# TRC_ESP8266_v5.net
KiCad netlist of a schematic drawn in EasyEDA
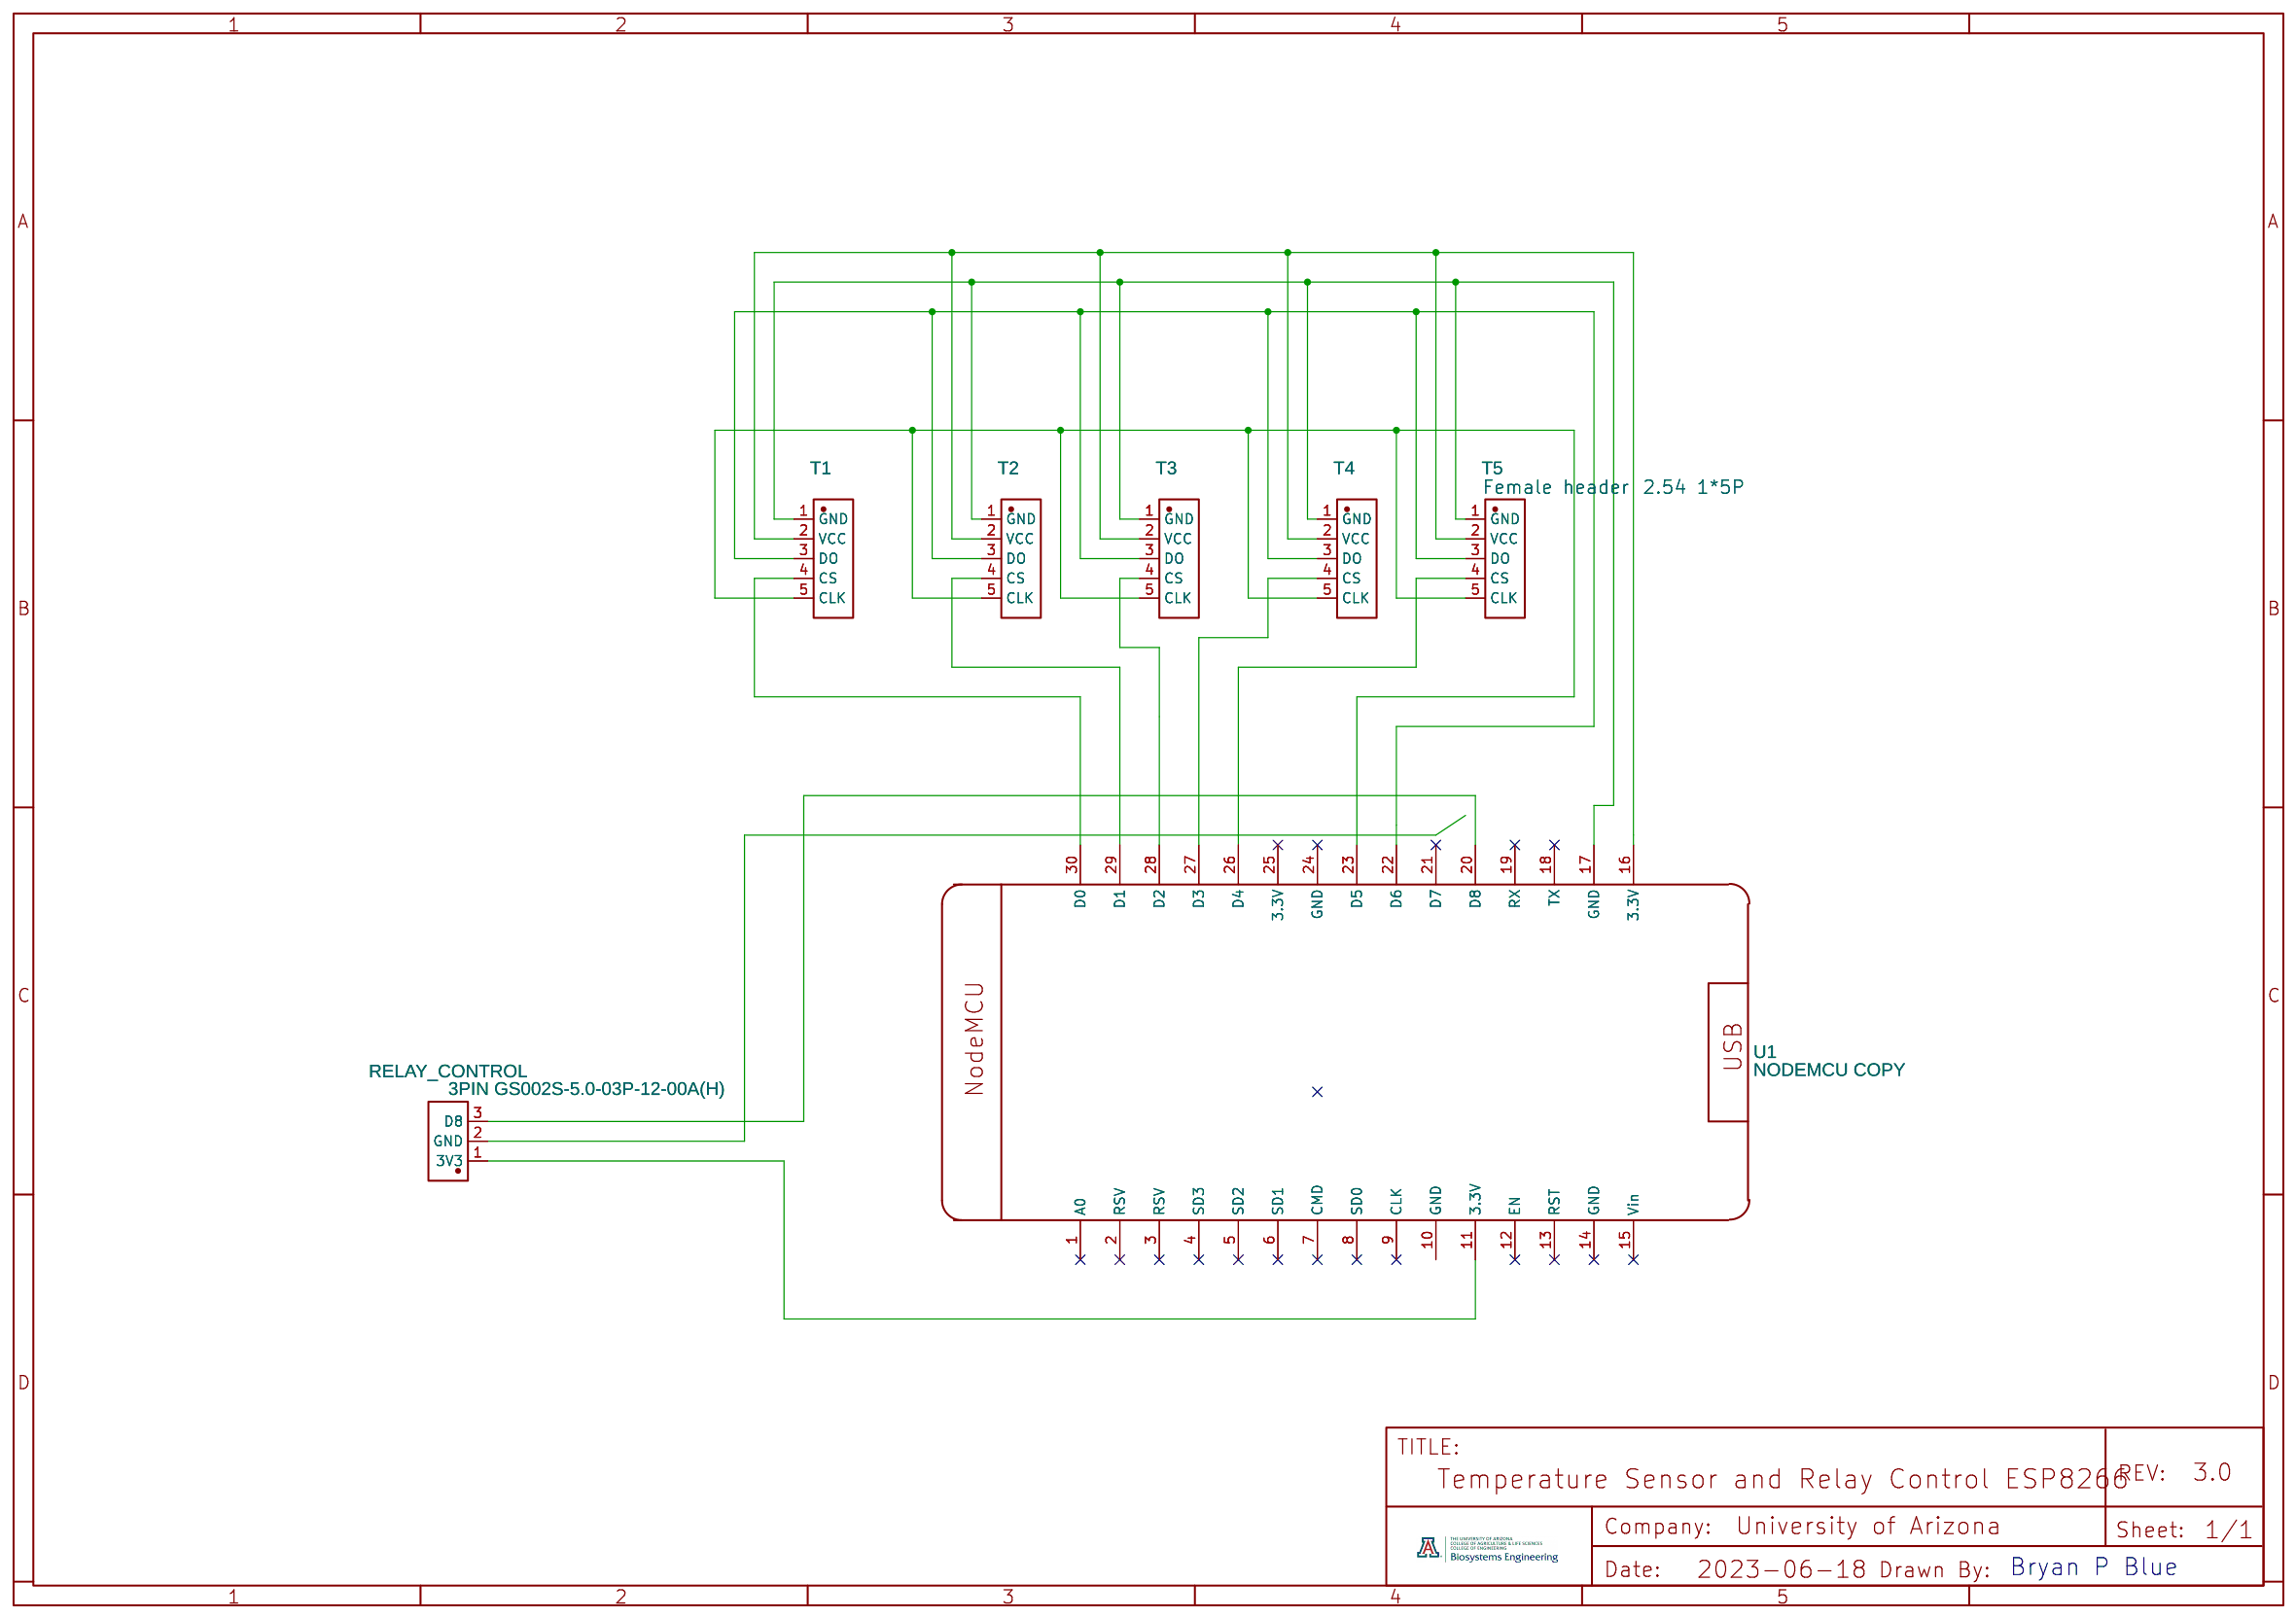
[diagram p0: schematic sheet]

(export (version "E")
  (design (tool "Eeschema 10.0.6"))
  (components
    (comp (ref "RELAY_CONTROL")
      (value "3PIN GS002S-5.0-03P-12-00A(H)")
      (fields
        (field (name "BOM_Manufacturer Part") "GS002S-5.0-03P-12-00A(H)")
        (field (name "BOM_Supplier Part") "C5142592")
      )
      (libsource (lib "") (part "3PIN клеммник винтовой GS002S-5.0-03P-12-00A(H)"))
    )
    (comp (ref "T1")
      (value "Female header　2.54 1*5Ｐ")
      (fields (field (name "BOM_Supplier Part") "C46341"))
      (libsource (lib "") (part "Female header　2.54 1*5Ｐ"))
    )
    (comp (ref "T2")
      (value "Female header　2.54 1*5Ｐ")
      (fields (field (name "BOM_Supplier Part") "C46341"))
      (libsource (lib "") (part "Female header　2.54 1*5Ｐ"))
    )
    (comp (ref "T3")
      (value "Female header　2.54 1*5Ｐ")
      (fields (field (name "BOM_Supplier Part") "C46341"))
      (libsource (lib "") (part "Female header　2.54 1*5Ｐ"))
    )
    (comp (ref "T4")
      (value "Female header　2.54 1*5Ｐ")
      (fields (field (name "BOM_Supplier Part") "C46341"))
      (libsource (lib "") (part "Female header　2.54 1*5Ｐ"))
    )
    (comp (ref "T5")
      (value "Female header　2.54 1*5Ｐ")
      (fields (field (name "BOM_Supplier Part") "C46341"))
      (libsource (lib "") (part "Female header　2.54 1*5Ｐ"))
    )
    (comp (ref "U1") (value "NODEMCU COPY") (libsource (lib "") (part "NODEMCU COPY")))
  )
  (nets
    (net (code "1") (name "Net-(RELAY_CONTROL-3V3)") (class "Default")
      (node (ref "RELAY_CONTROL") (pin "1") (pinfunction "3V3_1") (pintype "unspecified"))
      (node (ref "U1") (pin "11") (pinfunction "3.3V_11") (pintype "passive"))
    )
    (net (code "2") (name "Net-(RELAY_CONTROL-D8)") (class "Default")
      (node (ref "RELAY_CONTROL") (pin "3") (pinfunction "D8_3") (pintype "unspecified"))
      (node (ref "U1") (pin "20") (pinfunction "D8_20") (pintype "unspecified"))
    )
    (net (code "3") (name "Net-(T1-CLK)") (class "Default")
      (node (ref "T1") (pin "5") (pinfunction "CLK_5") (pintype "input"))
      (node (ref "T2") (pin "5") (pinfunction "CLK_5") (pintype "input"))
      (node (ref "T3") (pin "5") (pinfunction "CLK_5") (pintype "input"))
      (node (ref "T4") (pin "5") (pinfunction "CLK_5") (pintype "input"))
      (node (ref "T5") (pin "5") (pinfunction "CLK_5") (pintype "input"))
      (node (ref "U1") (pin "23") (pinfunction "D5_23") (pintype "unspecified"))
    )
    (net (code "4") (name "Net-(T1-CS)") (class "Default")
      (node (ref "T1") (pin "4") (pinfunction "CS_4") (pintype "input"))
      (node (ref "U1") (pin "30") (pinfunction "D0_30") (pintype "unspecified"))
    )
    (net (code "5") (name "Net-(T1-DO)") (class "Default")
      (node (ref "T1") (pin "3") (pinfunction "DO_3") (pintype "output"))
      (node (ref "T2") (pin "3") (pinfunction "DO_3") (pintype "output"))
      (node (ref "T3") (pin "3") (pinfunction "DO_3") (pintype "output"))
      (node (ref "T4") (pin "3") (pinfunction "DO_3") (pintype "output"))
      (node (ref "T5") (pin "3") (pinfunction "DO_3") (pintype "output"))
      (node (ref "U1") (pin "22") (pinfunction "D6_22") (pintype "unspecified"))
    )
    (net (code "6") (name "Net-(T1-GND)") (class "Default")
      (node (ref "T1") (pin "1") (pinfunction "GND_1") (pintype "passive"))
      (node (ref "T2") (pin "1") (pinfunction "GND_1") (pintype "passive"))
      (node (ref "T3") (pin "1") (pinfunction "GND_1") (pintype "passive"))
      (node (ref "T4") (pin "1") (pinfunction "GND_1") (pintype "passive"))
      (node (ref "T5") (pin "1") (pinfunction "GND_1") (pintype "passive"))
      (node (ref "U1") (pin "17") (pinfunction "GND_17") (pintype "passive"))
    )
    (net (code "7") (name "Net-(T1-VCC)") (class "Default")
      (node (ref "T1") (pin "2") (pinfunction "VCC_2") (pintype "passive"))
      (node (ref "T2") (pin "2") (pinfunction "VCC_2") (pintype "passive"))
      (node (ref "T3") (pin "2") (pinfunction "VCC_2") (pintype "passive"))
      (node (ref "T4") (pin "2") (pinfunction "VCC_2") (pintype "passive"))
      (node (ref "T5") (pin "2") (pinfunction "VCC_2") (pintype "passive"))
      (node (ref "U1") (pin "16") (pinfunction "3.3V_16") (pintype "passive"))
    )
    (net (code "8") (name "Net-(T2-CS)") (class "Default")
      (node (ref "T2") (pin "4") (pinfunction "CS_4") (pintype "input"))
      (node (ref "U1") (pin "29") (pinfunction "D1_29") (pintype "unspecified"))
    )
    (net (code "9") (name "Net-(T3-CS)") (class "Default")
      (node (ref "T3") (pin "4") (pinfunction "CS_4") (pintype "input"))
      (node (ref "U1") (pin "28") (pinfunction "D2_28") (pintype "unspecified"))
    )
    (net (code "10") (name "Net-(T4-CS)") (class "Default")
      (node (ref "T4") (pin "4") (pinfunction "CS_4") (pintype "input"))
      (node (ref "U1") (pin "27") (pinfunction "D3_27") (pintype "unspecified"))
    )
    (net (code "11") (name "Net-(T5-CS)") (class "Default")
      (node (ref "T5") (pin "4") (pinfunction "CS_4") (pintype "input"))
      (node (ref "U1") (pin "26") (pinfunction "D4_26") (pintype "unspecified"))
    )
    (net (code "12") (name "unconnected-(RELAY_CONTROL-GND-Pad2)") (class "Default")
      (node (ref "RELAY_CONTROL") (pin "2") (pinfunction "GND_2") (pintype "unspecified"))
    )
    (net (code "13") (name "unconnected-(U1-3.3V-Pad25)") (class "Default")
      (node (ref "U1") (pin "25") (pinfunction "3.3V_25") (pintype "passive+no_connect"))
    )
    (net (code "14") (name "unconnected-(U1-A0-Pad1)") (class "Default")
      (node (ref "U1") (pin "1") (pinfunction "A0_1") (pintype "unspecified+no_connect"))
    )
    (net (code "15") (name "unconnected-(U1-CLK-Pad9)") (class "Default")
      (node (ref "U1") (pin "9") (pinfunction "CLK_9") (pintype "output+no_connect"))
    )
    (net (code "16") (name "unconnected-(U1-CMD-Pad7)") (class "Default")
      (node (ref "U1") (pin "7") (pinfunction "CMD_7") (pintype "unspecified+no_connect"))
    )
    (net (code "17") (name "unconnected-(U1-D7-Pad21)") (class "Default")
      (node (ref "U1") (pin "21") (pinfunction "D7_21") (pintype "unspecified+no_connect"))
    )
    (net (code "18") (name "unconnected-(U1-EN-Pad12)") (class "Default")
      (node (ref "U1") (pin "12") (pinfunction "EN_12") (pintype "unspecified+no_connect"))
    )
    (net (code "19") (name "unconnected-(U1-GND-Pad10)") (class "Default")
      (node (ref "U1") (pin "10") (pinfunction "GND_10") (pintype "passive"))
    )
    (net (code "20") (name "unconnected-(U1-GND-Pad14)") (class "Default")
      (node (ref "U1") (pin "14") (pinfunction "GND_14") (pintype "passive+no_connect"))
    )
    (net (code "21") (name "unconnected-(U1-GND-Pad24)") (class "Default")
      (node (ref "U1") (pin "24") (pinfunction "GND_24") (pintype "passive+no_connect"))
    )
    (net (code "22") (name "unconnected-(U1-RST-Pad13)") (class "Default")
      (node (ref "U1") (pin "13") (pinfunction "RST_13") (pintype "unspecified+no_connect"))
    )
    (net (code "23") (name "unconnected-(U1-RSV-Pad2)") (class "Default")
      (node (ref "U1") (pin "2") (pinfunction "RSV_2") (pintype "unspecified+no_connect"))
    )
    (net (code "24") (name "unconnected-(U1-RSV-Pad3)") (class "Default")
      (node (ref "U1") (pin "3") (pinfunction "RSV_3") (pintype "unspecified+no_connect"))
    )
    (net (code "25") (name "unconnected-(U1-RX-Pad19)") (class "Default")
      (node (ref "U1") (pin "19") (pinfunction "RX_19") (pintype "unspecified+no_connect"))
    )
    (net (code "26") (name "unconnected-(U1-SD0-Pad8)") (class "Default")
      (node (ref "U1") (pin "8") (pinfunction "SD0_8") (pintype "unspecified+no_connect"))
    )
    (net (code "27") (name "unconnected-(U1-SD1-Pad6)") (class "Default")
      (node (ref "U1") (pin "6") (pinfunction "SD1_6") (pintype "unspecified+no_connect"))
    )
    (net (code "28") (name "unconnected-(U1-SD2-Pad5)") (class "Default")
      (node (ref "U1") (pin "5") (pinfunction "SD2_5") (pintype "unspecified+no_connect"))
    )
    (net (code "29") (name "unconnected-(U1-SD3-Pad4)") (class "Default")
      (node (ref "U1") (pin "4") (pinfunction "SD3_4") (pintype "unspecified+no_connect"))
    )
    (net (code "30") (name "unconnected-(U1-TX-Pad18)") (class "Default")
      (node (ref "U1") (pin "18") (pinfunction "TX_18") (pintype "unspecified+no_connect"))
    )
    (net (code "31") (name "unconnected-(U1-Vin-Pad15)") (class "Default")
      (node (ref "U1") (pin "15") (pinfunction "Vin_15") (pintype "passive+no_connect"))
    )
  )
)
